# GD_AirIrDA_485.net
KiCad netlist of a schematic drawn in Altium Designer
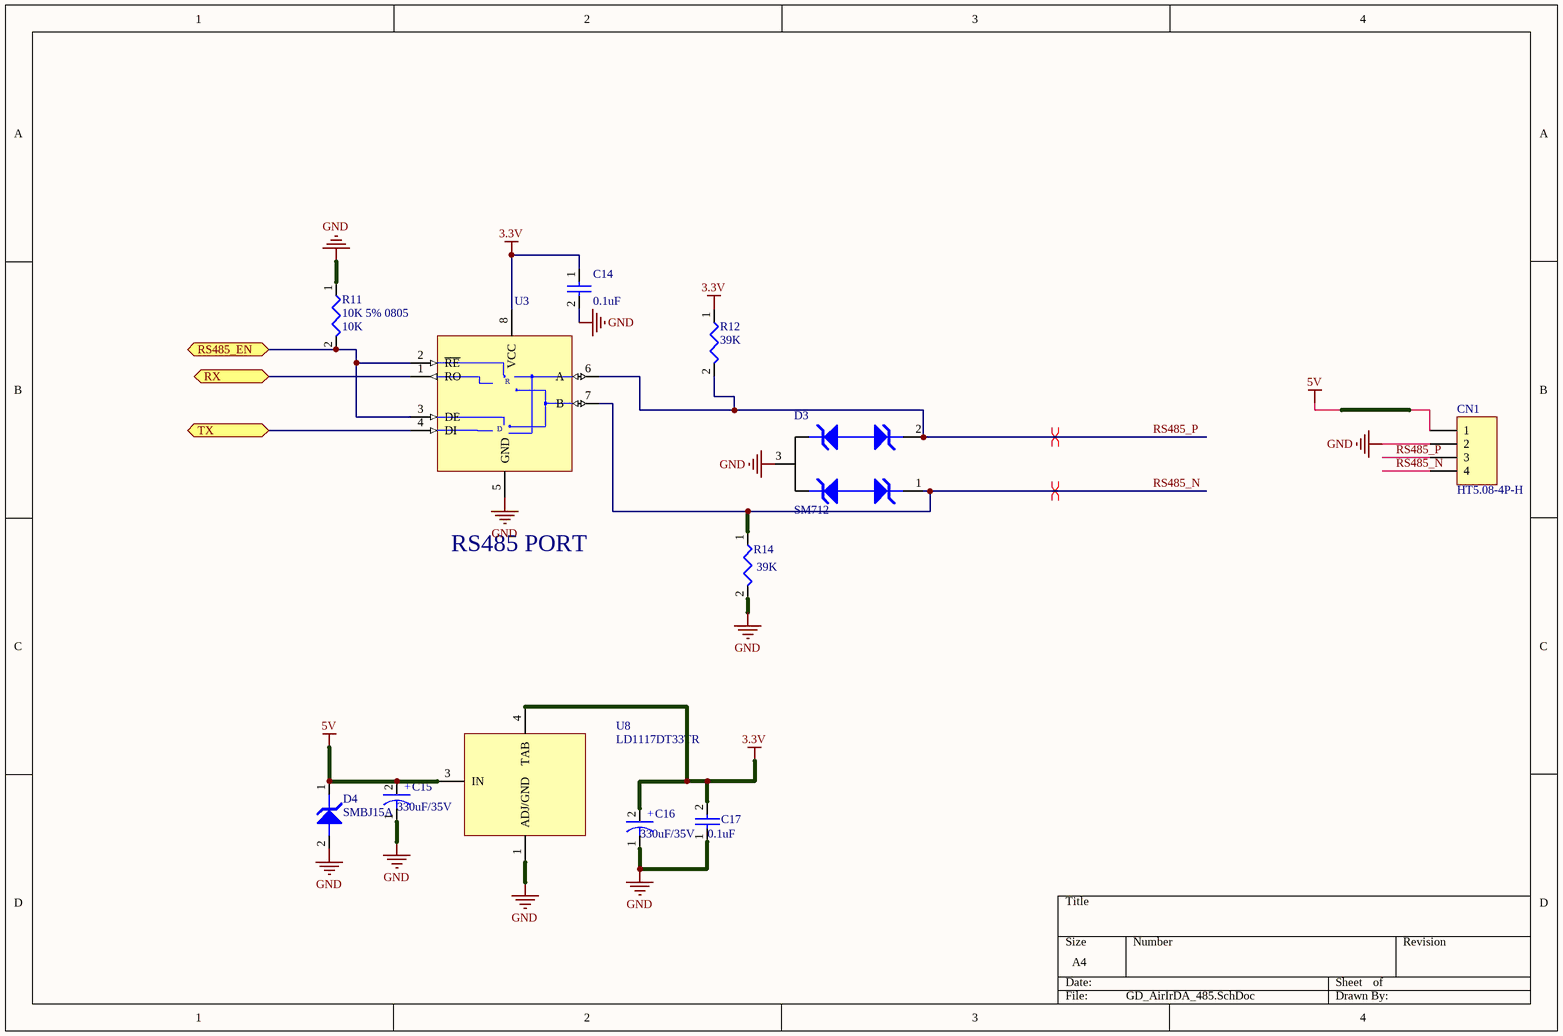
[diagram p0: GD_AirIrDA_485.SchDoc]

(export (version "E")
  (design (tool "Eeschema 10.0.6"))
  (components
    (comp (ref "C14")
      (value "0.1uF")
      (footprint "C0805")
      (description "CAP SMD CR X7R 50V 10% 0.1uF 0805 ROHS")
      (fields (field (name "MANUFACTURER") "YAGEO") (field (name "Comment") "CAP 0.1uF 20% 50V 0805"))
      (libsource (lib "enlogic") (part "CAP"))
    )
    (comp (ref "C15")
      (value "330uF/35V")
      (footprint "CA10X16P5")
      (description "CAP 35V 20% 330uF 10X16X0.6MM ROHS，7000hours")
      (fields
        (field (name "MANUFACTURER") "NIPPON CHEMI-CON")
        (field (name "Comment") "CAPACITOR 330uF 20% 35V 10mmX16mm")
      )
      (libsource (lib "Enlogic") (part "CAPACITOR"))
    )
    (comp (ref "C16")
      (value "330uF/35V")
      (footprint "CA10X16P5")
      (description "CAP 35V 20% 330uF 10X16X0.6MM ROHS，7000hours")
      (fields
        (field (name "MANUFACTURER") "NIPPON CHEMI-CON")
        (field (name "Comment") "CAPACITOR 330uF 20% 35V 10mmX16mm")
      )
      (libsource (lib "Enlogic") (part "CAPACITOR"))
    )
    (comp (ref "C17")
      (value "0.1uF")
      (footprint "C0805")
      (description "CAP SMD CR X7R 50V 10% 0.1uF 0805 ROHS")
      (fields (field (name "MANUFACTURER") "YAGEO") (field (name "Comment") "CAP 0.1uF 20% 50V 0805"))
      (libsource (lib "enlogic") (part "CAP"))
    )
    (comp (ref "CN1")
      (value "HT5.08-4P-H")
      (footprint "HT5.08-4P-H")
      (description "Header, 4-Pin")
      (libsource (lib "Enlogic_CN") (part "Header 4"))
    )
    (comp (ref "D3")
      (value "SM712")
      (footprint "SOT23-123")
      (description "DIODE TVS 7V 12V 17A 400W SOT-23 SMD ROHS")
      (fields (field (name "MANUFACTURER") "BOURNS"))
      (libsource (lib "enlogic") (part "TVS-D"))
    )
    (comp (ref "D4")
      (value "SMBJ15A")
      (footprint "SMB")
      (fields (field (name "MANUFACTURER") "Bourns"))
      (libsource (lib "Enlogic") (part "ZENER"))
    )
    (comp (ref "R11")
      (value "10K 5% 0805")
      (footprint "R0805")
      (description "RES THICK_FILM SMD 10K ohm 5% 1/10W ROHS 0603")
      (fields (field (name "MANUFACTURER") "YAGEO") (field (name "ALTIUM_VALUE") "10K"))
      (libsource (lib "Enlogic") (part "RES"))
    )
    (comp (ref "R12")
      (value "39K")
      (footprint "R0805")
      (description "RES THICK_FILM SMD 39K 5% 1/8W ROHS 0805")
      (fields (field (name "MANUFACTURER") "YAGEO") (field (name "Comment") "39K 5% 0805"))
      (libsource (lib "enlogic") (part "RES"))
    )
    (comp (ref "R14")
      (value "39K")
      (footprint "R0805")
      (description "RES THICK_FILM SMD 39K 5% 1/8W ROHS 0805")
      (fields (field (name "MANUFACTURER") "YAGEO") (field (name "Comment") "39K 5% 0805"))
      (libsource (lib "enlogic") (part "RES"))
    )
    (comp (ref "U3")
      (value "SN65HVD08D")
      (footprint "SOIC8")
      (description "IC 5V,RS-485,10Mbps,16KV,TRANSCEIVERS,SOIC-8,ROHS")
      (fields (field (name "MANUFACTURER") "Texas Instruments"))
      (libsource (lib "enlogic") (part "SN65HVD11D"))
    )
    (comp (ref "U8")
      (value "LD1117DT33TR")
      (footprint "DPAK-134")
      (description "IC REG VOLT +3.3V LDO 800MA DPAK ROHS")
      (fields (field (name "MANUFACTURER") "ST"))
      (libsource (lib "Enlogic") (part "LM1117_ADJ"))
    )
  )
  (nets
    (net (code "1") (name "/RS485_EN") (class "Default")
      (node (ref "R11") (pin "2") (pinfunction "2_2") (pintype "passive"))
      (node (ref "U3") (pin "2") (pinfunction "~{RE}_2") (pintype "input"))
      (node (ref "U3") (pin "3") (pinfunction "DE_3") (pintype "input"))
    )
    (net (code "2") (name "/RS485_N") (class "Default")
      (node (ref "CN1") (pin "4") (pinfunction "4_4") (pintype "passive"))
      (node (ref "D3") (pin "1") (pinfunction "1_1") (pintype "passive"))
      (node (ref "R14") (pin "1") (pinfunction "1_1") (pintype "passive"))
      (node (ref "U3") (pin "7") (pinfunction "B_7") (pintype "bidirectional"))
    )
    (net (code "3") (name "/RS485_P") (class "Default")
      (node (ref "CN1") (pin "3") (pinfunction "3_3") (pintype "passive"))
      (node (ref "D3") (pin "2") (pinfunction "2_2") (pintype "passive"))
      (node (ref "R12") (pin "2") (pinfunction "2_2") (pintype "passive"))
      (node (ref "U3") (pin "6") (pinfunction "A_6") (pintype "bidirectional"))
    )
    (net (code "4") (name "/RX") (class "Default")
      (node (ref "U3") (pin "1") (pinfunction "RO_1") (pintype "output"))
    )
    (net (code "5") (name "/TX") (class "Default")
      (node (ref "U3") (pin "4") (pinfunction "DI_4") (pintype "input"))
    )
    (net (code "6") (name "3.3V") (class "Default")
      (node (ref "C14") (pin "1") (pinfunction "1_1") (pintype "passive"))
      (node (ref "C16") (pin "2") (pinfunction "2_2") (pintype "passive"))
      (node (ref "C17") (pin "2") (pinfunction "2_2") (pintype "passive"))
      (node (ref "R12") (pin "1") (pinfunction "1_1") (pintype "passive"))
      (node (ref "U3") (pin "8") (pinfunction "VCC_8") (pintype "power_in"))
      (node (ref "U8") (pin "4") (pinfunction "TAB_4") (pintype "passive"))
    )
    (net (code "7") (name "5V") (class "Default")
      (node (ref "C15") (pin "2") (pinfunction "2_2") (pintype "passive"))
      (node (ref "CN1") (pin "1") (pinfunction "1_1") (pintype "passive"))
      (node (ref "D4") (pin "1") (pintype "passive"))
      (node (ref "U8") (pin "3") (pinfunction "IN_3") (pintype "passive"))
    )
    (net (code "8") (name "GND") (class "Default")
      (node (ref "C14") (pin "2") (pinfunction "2_2") (pintype "passive"))
      (node (ref "C15") (pin "1") (pinfunction "1_1") (pintype "passive"))
      (node (ref "C16") (pin "1") (pinfunction "1_1") (pintype "passive"))
      (node (ref "C17") (pin "1") (pinfunction "1_1") (pintype "passive"))
      (node (ref "CN1") (pin "2") (pinfunction "2_2") (pintype "passive"))
      (node (ref "D3") (pin "3") (pinfunction "3_3") (pintype "passive"))
      (node (ref "D4") (pin "2") (pintype "passive"))
      (node (ref "R11") (pin "1") (pinfunction "1_1") (pintype "passive"))
      (node (ref "R14") (pin "2") (pinfunction "2_2") (pintype "passive"))
      (node (ref "U3") (pin "5") (pinfunction "GND_5") (pintype "power_in"))
      (node (ref "U8") (pin "1") (pinfunction "ADJ/GND_1") (pintype "passive"))
    )
  )
)
